# MotorBoard.net
KiCad netlist of a schematic drawn in EAGLE
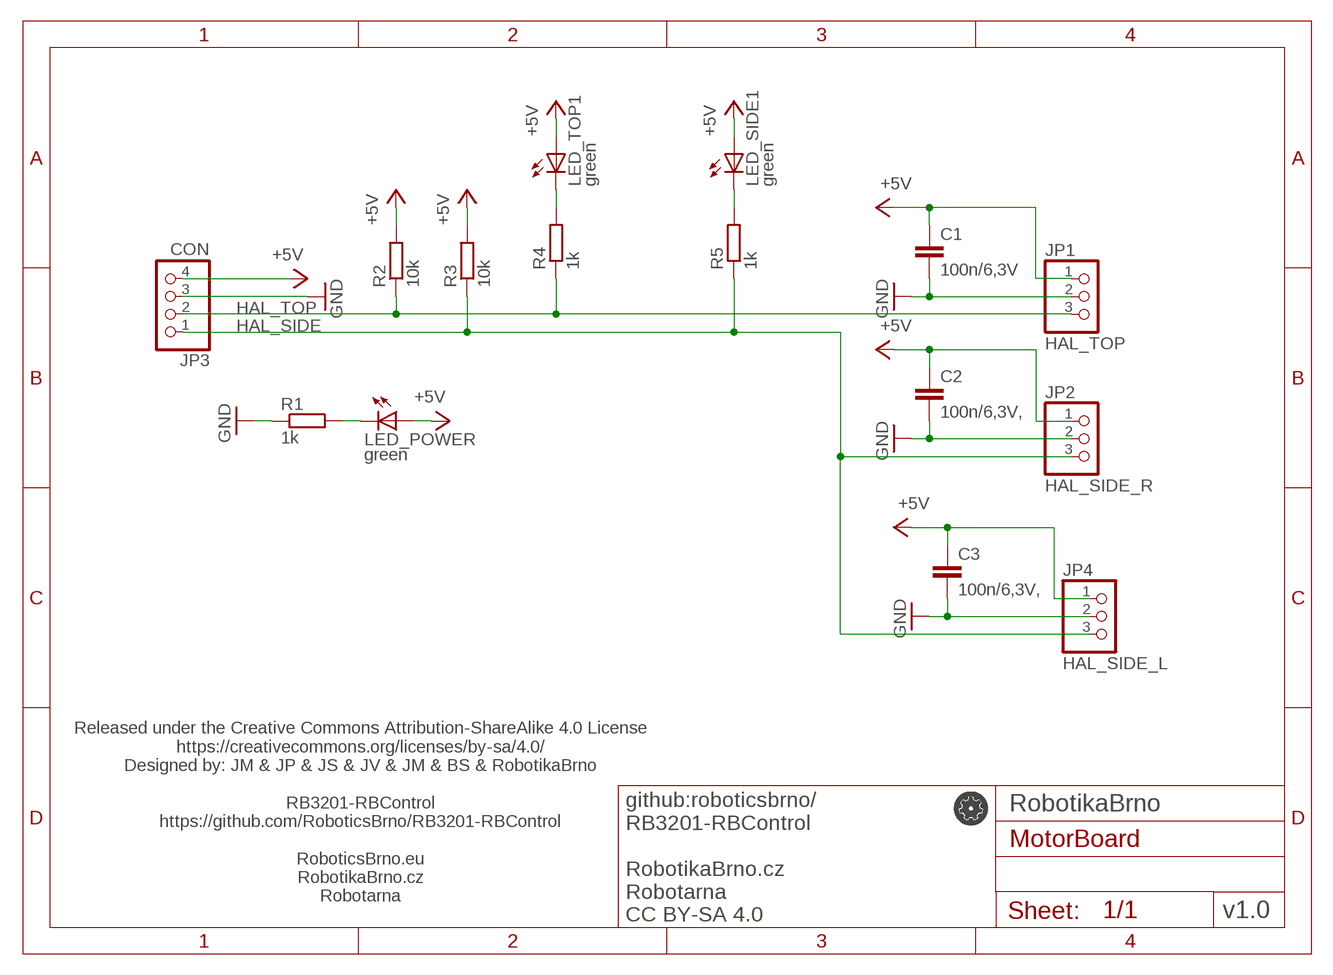
[diagram p0: schematic, sheet 1]

(export (version "E")
  (design (tool "Eeschema 10.0.6"))
  (components
    (comp (ref "C1")
      (value "100n/6,3V")
      (footprint "eagle-import:C0603")
      (libsource (lib "eagle-import") (part "C-EUC0603"))
    )
    (comp (ref "C2")
      (value "100n/6,3V,")
      (footprint "eagle-import:C0603")
      (libsource (lib "eagle-import") (part "C-EUC0603"))
    )
    (comp (ref "C3")
      (value "100n/6,3V,")
      (footprint "eagle-import:C0603")
      (libsource (lib "eagle-import") (part "C-EUC0603"))
    )
    (comp (ref "JP1")
      (value "HAL_TOP")
      (footprint "eagle-import:1X03_90")
      (libsource (lib "eagle-import") (part "PINHD-1X3/90"))
    )
    (comp (ref "JP2")
      (value "HAL_SIDE_R")
      (footprint "eagle-import:1X03_90")
      (libsource (lib "eagle-import") (part "PINHD-1X3/90"))
    )
    (comp (ref "JP3")
      (value "CON")
      (footprint "eagle-import:1X04_90")
      (libsource (lib "eagle-import") (part "PINHD-1X4/90"))
    )
    (comp (ref "JP4")
      (value "HAL_SIDE_L")
      (footprint "eagle-import:1X03_90")
      (libsource (lib "eagle-import") (part "PINHD-1X3/90"))
    )
    (comp (ref "LED_POWER")
      (value "green")
      (footprint "eagle-import:CHIPLED_0603")
      (libsource (lib "eagle-import") (part "LEDCHIPLED_0603"))
    )
    (comp (ref "LED_SIDE1")
      (value "green")
      (footprint "eagle-import:CHIPLED_0603")
      (libsource (lib "eagle-import") (part "LEDCHIPLED_0603"))
    )
    (comp (ref "LED_TOP1")
      (value "green")
      (footprint "eagle-import:CHIPLED_0603")
      (libsource (lib "eagle-import") (part "LEDCHIPLED_0603"))
    )
    (comp (ref "R1")
      (value "1k")
      (footprint "eagle-import:R0603")
      (libsource (lib "eagle-import") (part "R-EU_R0603"))
    )
    (comp (ref "R2")
      (value "10k")
      (footprint "eagle-import:R0603")
      (libsource (lib "eagle-import") (part "R-EU_R0603"))
    )
    (comp (ref "R3")
      (value "10k")
      (footprint "eagle-import:R0603")
      (libsource (lib "eagle-import") (part "R-EU_R0603"))
    )
    (comp (ref "R4")
      (value "1k")
      (footprint "eagle-import:R0603")
      (libsource (lib "eagle-import") (part "R-EU_R0603"))
    )
    (comp (ref "R5")
      (value "1k")
      (footprint "eagle-import:R0603")
      (libsource (lib "eagle-import") (part "R-EU_R0603"))
    )
  )
  (nets
    (net (code "1") (name "+5V") (class "Default")
      (node (ref "C1") (pin "1") (pinfunction "1_1") (pintype "passive"))
      (node (ref "C2") (pin "1") (pinfunction "1_1") (pintype "passive"))
      (node (ref "C3") (pin "1") (pinfunction "1_1") (pintype "passive"))
      (node (ref "JP1") (pin "1") (pinfunction "1_1") (pintype "passive"))
      (node (ref "JP2") (pin "1") (pinfunction "1_1") (pintype "passive"))
      (node (ref "JP3") (pin "4") (pinfunction "4_4") (pintype "passive"))
      (node (ref "JP4") (pin "1") (pinfunction "1_1") (pintype "passive"))
      (node (ref "LED_POWER") (pin "A") (pinfunction "A_A") (pintype "passive"))
      (node (ref "LED_SIDE1") (pin "A") (pinfunction "A_A") (pintype "passive"))
      (node (ref "LED_TOP1") (pin "A") (pinfunction "A_A") (pintype "passive"))
      (node (ref "R2") (pin "2") (pinfunction "2_2") (pintype "passive"))
      (node (ref "R3") (pin "2") (pinfunction "2_2") (pintype "passive"))
    )
    (net (code "2") (name "/HAL_SIDE") (class "Default")
      (node (ref "JP2") (pin "3") (pinfunction "3_3") (pintype "passive"))
      (node (ref "JP3") (pin "1") (pinfunction "1_1") (pintype "passive"))
      (node (ref "JP4") (pin "3") (pinfunction "3_3") (pintype "passive"))
      (node (ref "R3") (pin "1") (pinfunction "1_1") (pintype "passive"))
      (node (ref "R5") (pin "1") (pinfunction "1_1") (pintype "passive"))
    )
    (net (code "3") (name "/HAL_TOP") (class "Default")
      (node (ref "JP1") (pin "3") (pinfunction "3_3") (pintype "passive"))
      (node (ref "JP3") (pin "2") (pinfunction "2_2") (pintype "passive"))
      (node (ref "R2") (pin "1") (pinfunction "1_1") (pintype "passive"))
      (node (ref "R4") (pin "1") (pinfunction "1_1") (pintype "passive"))
    )
    (net (code "4") (name "GND") (class "Default")
      (node (ref "C1") (pin "2") (pinfunction "2_2") (pintype "passive"))
      (node (ref "C2") (pin "2") (pinfunction "2_2") (pintype "passive"))
      (node (ref "C3") (pin "2") (pinfunction "2_2") (pintype "passive"))
      (node (ref "JP1") (pin "2") (pinfunction "2_2") (pintype "passive"))
      (node (ref "JP2") (pin "2") (pinfunction "2_2") (pintype "passive"))
      (node (ref "JP3") (pin "3") (pinfunction "3_3") (pintype "passive"))
      (node (ref "JP4") (pin "2") (pinfunction "2_2") (pintype "passive"))
      (node (ref "R1") (pin "1") (pinfunction "1_1") (pintype "passive"))
    )
    (net (code "5") (name "Net-(LED_POWER-PadC)") (class "Default")
      (node (ref "LED_POWER") (pin "C") (pinfunction "C_C") (pintype "passive"))
      (node (ref "R1") (pin "2") (pinfunction "2_2") (pintype "passive"))
    )
    (net (code "6") (name "Net-(LED_SIDE1-PadC)") (class "Default")
      (node (ref "LED_SIDE1") (pin "C") (pinfunction "C_C") (pintype "passive"))
      (node (ref "R5") (pin "2") (pinfunction "2_2") (pintype "passive"))
    )
    (net (code "7") (name "Net-(LED_TOP1-PadC)") (class "Default")
      (node (ref "LED_TOP1") (pin "C") (pinfunction "C_C") (pintype "passive"))
      (node (ref "R4") (pin "2") (pinfunction "2_2") (pintype "passive"))
    )
  )
)
